# Buck_Converter.net
KiCad netlist of a schematic drawn in Altium Designer
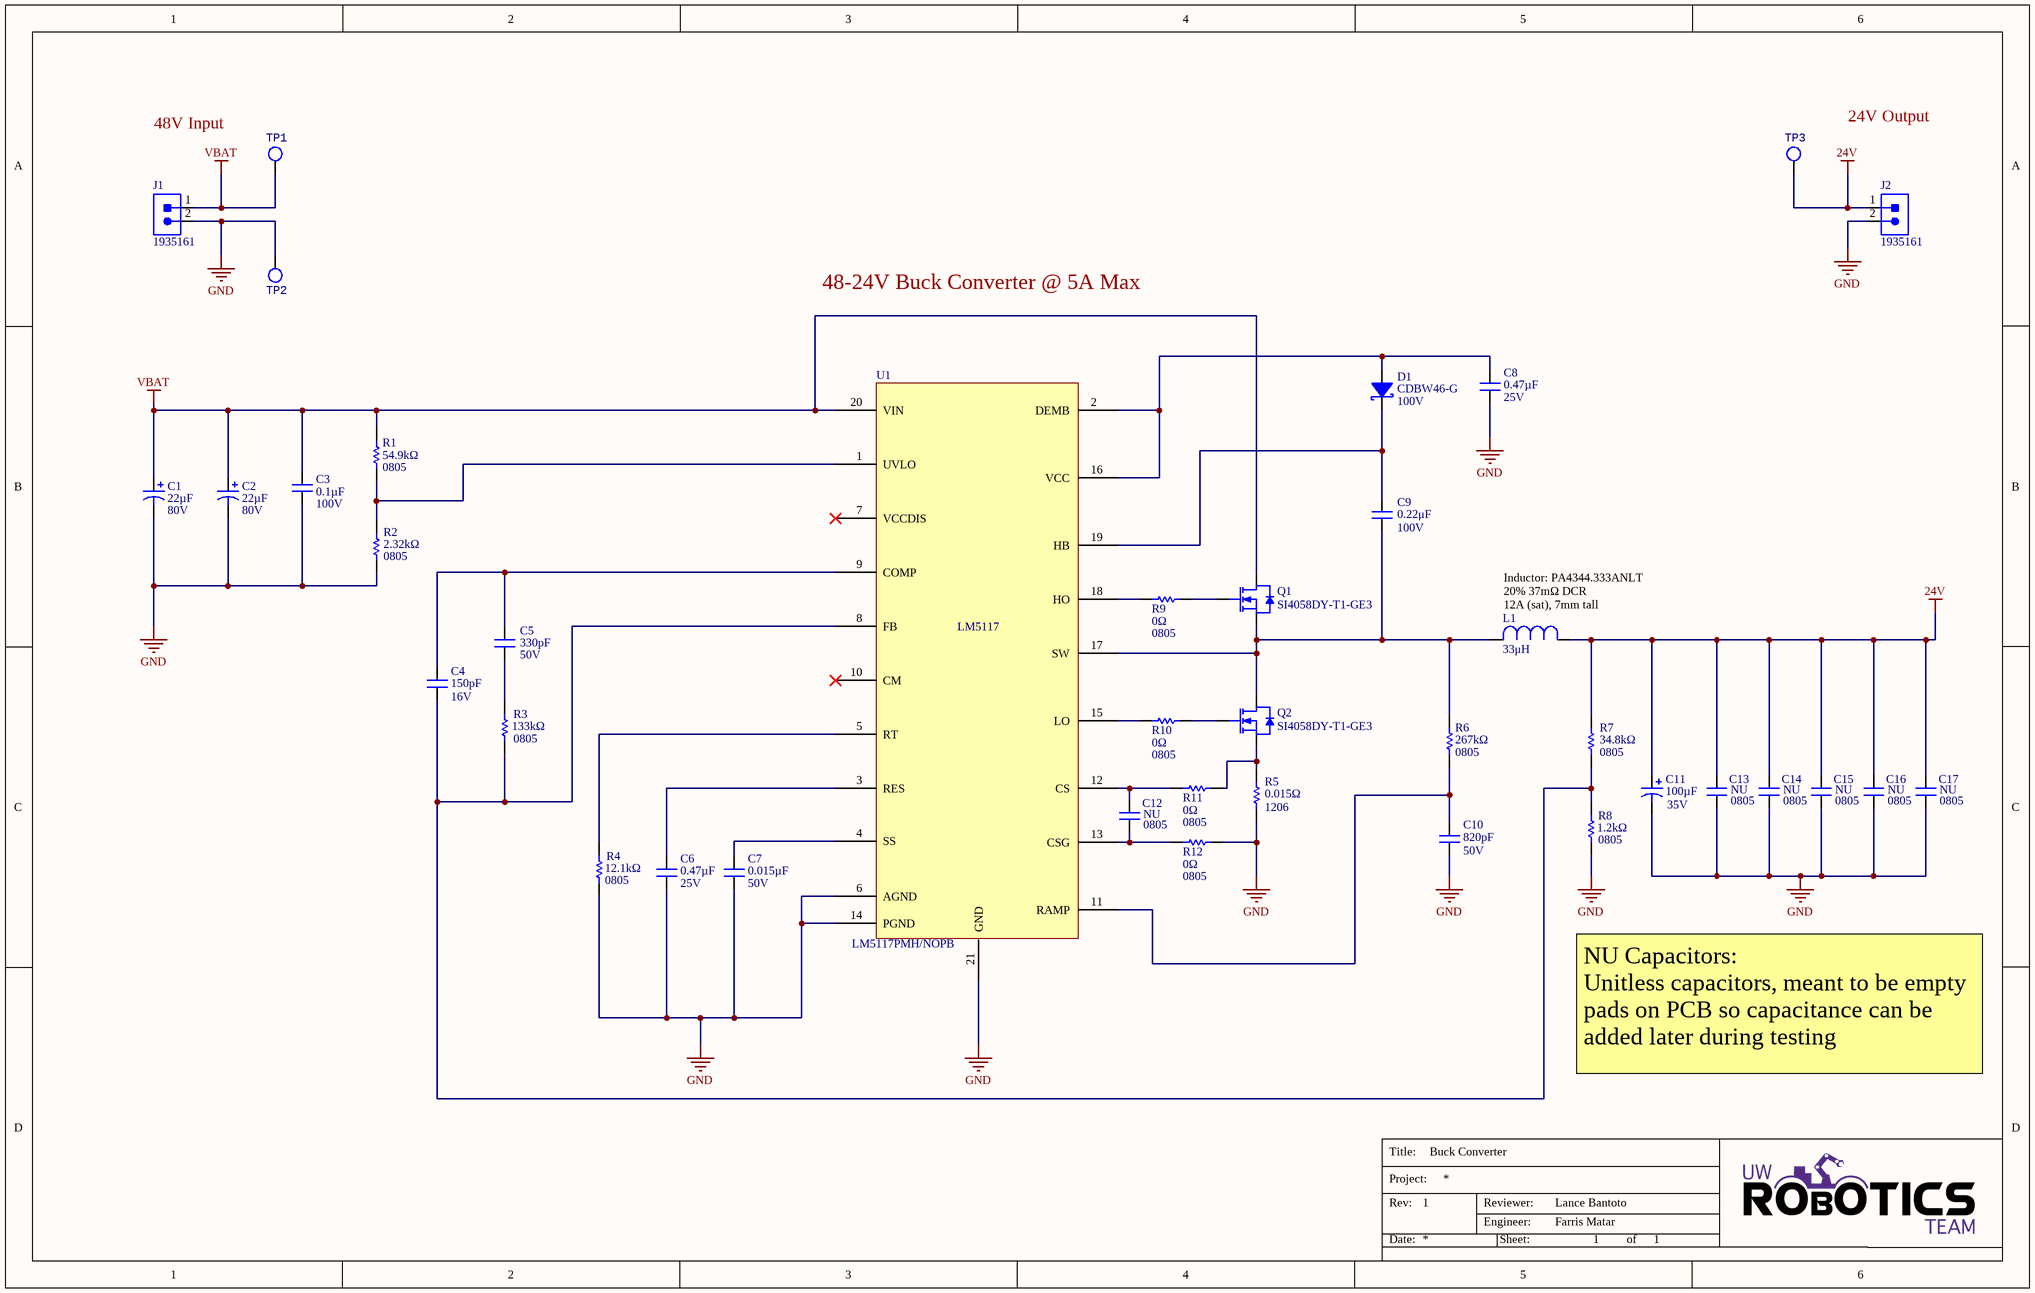
[diagram p0: Buck Converter.SchDoc]

(export (version "E")
  (design (tool "Eeschema 10.0.6"))
  (components
    (comp (ref "C1")
      (value "22µF")
      (footprint "RADIAL_PANASONIC_F")
      (description "CAP ALUM POLY 22UF 20% 80V SMD")
      (fields (field (name "VOLTAGE RATING") "80V") (field (name "Comment") "CAP_22uF_80V_ALUM"))
      (libsource (lib "UWRT_Schematic_Library_2020") (part "CAP_22uF_80V_ALUM"))
    )
    (comp (ref "C2")
      (value "22µF")
      (footprint "RADIAL_PANASONIC_F")
      (description "CAP ALUM POLY 22UF 20% 80V SMD")
      (fields (field (name "VOLTAGE RATING") "80V") (field (name "Comment") "CAP_22uF_80V_ALUM"))
      (libsource (lib "UWRT_Schematic_Library_2020") (part "CAP_22uF_80V_ALUM"))
    )
    (comp (ref "C3")
      (value "0.1µF")
      (footprint "CAP0805")
      (description "CAP CER 0.1UF 100V X7R 0805")
      (fields (field (name "VOLTAGE RATING") "100V") (field (name "Comment") "CAP_0.1uF_100V_0805"))
      (libsource (lib "UWRT_Schematic_Library_2020") (part "CAP_0.1uF_100V_0805"))
    )
    (comp (ref "C4")
      (value "150pF")
      (footprint "CAP0805")
      (description "CAP CER 150PF 16V X7R 0805")
      (fields (field (name "VOLTAGE RATING") "16V") (field (name "Comment") "CAP_150pF_16V_0805"))
      (libsource (lib "UWRT_Schematic_Library_2020") (part "CAP_150pF_16V_0805"))
    )
    (comp (ref "C5")
      (value "330pF")
      (footprint "CAP0805")
      (description "CAP CER 330PF 50V C0G/NPO 0805")
      (fields (field (name "VOLTAGE RATING") "50V") (field (name "Comment") "CAP_330pF_50V_0805"))
      (libsource (lib "UWRT_Schematic_Library_2020") (part "CAP_330pF_50V_0805"))
    )
    (comp (ref "C6")
      (value "0.47µF")
      (footprint "CAP0805")
      (description "CAP CER 0.47UF 25V X5R 0805")
      (fields (field (name "VOLTAGE RATING") "25V") (field (name "Comment") "CAP_0.47uF_25V_0805"))
      (libsource (lib "UWRT_Schematic_Library_2020") (part "CAP_0.47uF_25V_0805"))
    )
    (comp (ref "C7")
      (value "0.015µF")
      (footprint "CAP0805")
      (description "CAP CER 0.015UF 50V C0G 0805")
      (fields (field (name "VOLTAGE RATING") "50V") (field (name "Comment") "CAP_0.015uF_50V_0805"))
      (libsource (lib "UWRT_Schematic_Library_2020") (part "CAP_0.015uF_50V_0805"))
    )
    (comp (ref "C8")
      (value "0.47µF")
      (footprint "CAP0805")
      (description "CAP CER 0.47UF 25V X5R 0805")
      (fields (field (name "VOLTAGE RATING") "25V") (field (name "Comment") "CAP_0.47uF_25V_0805"))
      (libsource (lib "UWRT_Schematic_Library_2020") (part "CAP_0.47uF_25V_0805"))
    )
    (comp (ref "C9")
      (value "0.22μF")
      (footprint "CAP2012")
      (description "CAP CER 0.22UF 100V X7R 0805")
      (fields (field (name "VOLTAGE RATING") "100V") (field (name "Comment") "CAP_0.22uF_100V_0805"))
      (libsource (lib "UWRT_Schematic_Library_2020") (part "CAP_0.22uF_100V_0805"))
    )
    (comp (ref "C10")
      (value "820pF")
      (footprint "CAP0805")
      (description "CAP CER 820PF 50V C0G/NP0 0805")
      (fields (field (name "VOLTAGE RATING") "50V") (field (name "Comment") "CAP_820pF_50V_0805"))
      (libsource (lib "UWRT_Schematic_Library_2020") (part "CAP_820pF_50V_0805"))
    )
    (comp (ref "C11")
      (value "100µF")
      (footprint "RADIAL_CORNELL_D")
      (description "CAP ALUM 100UF 20% 35V SMD")
      (fields (field (name "VOLTAGE RATING") "35V") (field (name "Comment") "CAP_100uF_35V_ALUM"))
      (libsource (lib "UWRT_Schematic_Library_2020") (part "CAP_100uF_35V_ALUM"))
    )
    (comp (ref "C12")
      (value "NU")
      (footprint "CAP0805")
      (description "PLACEHOLDER CAPACITOR 0805")
      (fields (field (name "PACKAGE/FOOTPRINT") "0805") (field (name "Comment") "CAP_NU_0805"))
      (libsource (lib "UWRT_Schematic_Library_2020") (part "CAP_NU_0805"))
    )
    (comp (ref "C13")
      (value "NU")
      (footprint "CAP0805")
      (description "PLACEHOLDER CAPACITOR 0805")
      (fields (field (name "PACKAGE/FOOTPRINT") "0805") (field (name "Comment") "CAP_NU_0805"))
      (libsource (lib "UWRT_Schematic_Library_2020") (part "CAP_NU_0805"))
    )
    (comp (ref "C14")
      (value "NU")
      (footprint "CAP0805")
      (description "PLACEHOLDER CAPACITOR 0805")
      (fields (field (name "PACKAGE/FOOTPRINT") "0805") (field (name "Comment") "CAP_NU_0805"))
      (libsource (lib "UWRT_Schematic_Library_2020") (part "CAP_NU_0805"))
    )
    (comp (ref "C15")
      (value "NU")
      (footprint "CAP0805")
      (description "PLACEHOLDER CAPACITOR 0805")
      (fields (field (name "PACKAGE/FOOTPRINT") "0805") (field (name "Comment") "CAP_NU_0805"))
      (libsource (lib "UWRT_Schematic_Library_2020") (part "CAP_NU_0805"))
    )
    (comp (ref "C16")
      (value "NU")
      (footprint "CAP0805")
      (description "PLACEHOLDER CAPACITOR 0805")
      (fields (field (name "PACKAGE/FOOTPRINT") "0805") (field (name "Comment") "CAP_NU_0805"))
      (libsource (lib "UWRT_Schematic_Library_2020") (part "CAP_NU_0805"))
    )
    (comp (ref "C17")
      (value "NU")
      (footprint "CAP0805")
      (description "PLACEHOLDER CAPACITOR 0805")
      (fields (field (name "PACKAGE/FOOTPRINT") "0805") (field (name "Comment") "CAP_NU_0805"))
      (libsource (lib "UWRT_Schematic_Library_2020") (part "CAP_NU_0805"))
    )
    (comp (ref "D1")
      (value "DIO_SCHOTTKY_100V_150mA")
      (footprint "SOD-123_FLAT")
      (description "DIODE SCHOTTKY 100V 150MA SOD123")
      (fields (field (name "MANUFACTURER PART NUMBER 1") "CDBW46-G") (field (name "VR (MAX)") "100V"))
      (libsource (lib "UWRT_Schematic_Library_2020") (part "DIO_SCHOTTKY_100V_150mA"))
    )
    (comp (ref "J1")
      (value "CON_2POS_SCREW_TERM")
      (footprint "1935161")
      (description "TERM BLK 2POS SIDE ENTRY 5MM")
      (fields (field (name "MANUFACTURER PART NUMBER 1") "1935161"))
      (libsource (lib "") (part "CON_2POS_SCREW_TERM_1"))
    )
    (comp (ref "J2")
      (value "CON_2POS_SCREW_TERM")
      (footprint "1935161")
      (description "TERM BLK 2POS SIDE ENTRY 5MM")
      (fields (field (name "MANUFACTURER PART NUMBER 1") "1935161"))
      (libsource (lib "UWRT_Schematic_Library_2020") (part "CON_2POS_SCREW_TERM"))
    )
    (comp (ref "L1")
      (value "IND_33uH_12.0A")
      (footprint "IND_PULSE_PA4344")
      (description "FIXED IND 33UH 12A 37 MOHM SMD")
      (fields (field (name "INDUCTANCE") "33μH"))
      (libsource (lib "UWRT_Schematic_Library_2020") (part "IND_33uH_12.0A"))
    )
    (comp (ref "Q1")
      (value "NMOS_100V_10.3A")
      (footprint "8-SOIC_NMOS")
      (description "MOSFET N-CH 100V 10.3A 8SOIC")
      (fields (field (name "MANUFACTURER PART NUMBER 1") "SI4058DY-T1-GE3"))
      (libsource (lib "UWRT_Schematic_Library_2020") (part "NMOS_100V_10.3A"))
    )
    (comp (ref "Q2")
      (value "NMOS_100V_10.3A")
      (footprint "8-SOIC_NMOS")
      (description "MOSFET N-CH 100V 10.3A 8SOIC")
      (fields (field (name "MANUFACTURER PART NUMBER 1") "SI4058DY-T1-GE3"))
      (libsource (lib "UWRT_Schematic_Library_2020") (part "NMOS_100V_10.3A"))
    )
    (comp (ref "R1")
      (value "54.9kΩ")
      (footprint "RES0805")
      (description "RES SMD 54.9K OHM 1% 1/8W 0805")
      (fields (field (name "PACKAGE/FOOTPRINT") "0805") (field (name "Comment") "RES_54.9kΩ_0805_1%"))
      (libsource (lib "UWRT_Schematic_Library_2020") (part "RES_54.9kΩ_0805_1%"))
    )
    (comp (ref "R2")
      (value "2.32kΩ")
      (footprint "RES0805")
      (description "RES 2.32K OHM 1% 1/4W 0805")
      (fields (field (name "PACKAGE/FOOTPRINT") "0805") (field (name "Comment") "RES_2.32kΩ_0805_1%"))
      (libsource (lib "UWRT_Schematic_Library_2020") (part "RES_2.32kΩ_0805_1%"))
    )
    (comp (ref "R3")
      (value "133kΩ")
      (footprint "RES0805")
      (description "RES SMD 133K OHM 1% 1/8W 0805")
      (fields (field (name "PACKAGE/FOOTPRINT") "0805") (field (name "Comment") "RES_133kΩ_0805_1%"))
      (libsource (lib "UWRT_Schematic_Library_2020") (part "RES_133kΩ_0805_1%"))
    )
    (comp (ref "R4")
      (value "12.1kΩ")
      (footprint "RES0805")
      (description "RES 12.1K OHM 1% 1/4W 0805")
      (fields (field (name "PACKAGE/FOOTPRINT") "0805") (field (name "Comment") "RES_12.1kΩ_0805_1%"))
      (libsource (lib "UWRT_Schematic_Library_2020") (part "RES_12.1kΩ_0805_1%"))
    )
    (comp (ref "R5")
      (value "0.015Ω")
      (footprint "RES1206")
      (description "RES 0.015 OHM 1% 1/2W 1206")
      (fields (field (name "PACKAGE/FOOTPRINT") "1206") (field (name "Comment") "RES_0.015Ω_1206_1%"))
      (libsource (lib "UWRT_Schematic_Library_2020") (part "RES_0.015Ω_1206_1%"))
    )
    (comp (ref "R6")
      (value "267kΩ")
      (footprint "RES0805")
      (description "RES SMD 267K OHM 1% 1/8W 0805")
      (fields (field (name "PACKAGE/FOOTPRINT") "0805") (field (name "Comment") "RES_267kΩ_0805_1%"))
      (libsource (lib "UWRT_Schematic_Library_2020") (part "RES_267kΩ_0805_1%"))
    )
    (comp (ref "R7")
      (value "34.8kΩ")
      (footprint "RES0805")
      (description "RES 34.8K OHM 1% 1/8W 0805")
      (fields (field (name "PACKAGE/FOOTPRINT") "0805") (field (name "Comment") "RES_34.8kΩ_0805_1%"))
      (libsource (lib "UWRT_Schematic_Library_2020") (part "RES_34.8kΩ_0805_1%"))
    )
    (comp (ref "R8")
      (value "1.2kΩ")
      (footprint "RES0805")
      (description "RES SMD 1.2K OHM 1% 1/8W 0805")
      (fields (field (name "PACKAGE/FOOTPRINT") "0805") (field (name "Comment") "RES_1.2kΩ_0805"))
      (libsource (lib "UWRT_Schematic_Library_2020") (part "RES_1.2kΩ_0805_1%"))
    )
    (comp (ref "R9")
      (value "0Ω")
      (footprint "RES0805")
      (description "RES 0 OHM JUMPER 1/8W 0805")
      (fields
        (field (name "PACKAGE/FOOTPRINT") "0805")
        (field (name "LCSC PART #") "C17477")
        (field (name "Comment") "RES_0Ω_0805")
      )
      (libsource (lib "UWRT_Schematic_Library_2020") (part "RES_0Ω_0805"))
    )
    (comp (ref "R10")
      (value "0Ω")
      (footprint "RES0805")
      (description "RES 0 OHM JUMPER 1/8W 0805")
      (fields
        (field (name "PACKAGE/FOOTPRINT") "0805")
        (field (name "LCSC PART #") "C17477")
        (field (name "Comment") "RES_0Ω_0805")
      )
      (libsource (lib "UWRT_Schematic_Library_2020") (part "RES_0Ω_0805"))
    )
    (comp (ref "R11")
      (value "0Ω")
      (footprint "RES0805")
      (description "RES 0 OHM JUMPER 1/8W 0805")
      (fields
        (field (name "PACKAGE/FOOTPRINT") "0805")
        (field (name "LCSC PART #") "C17477")
        (field (name "Comment") "RES_0Ω_0805")
      )
      (libsource (lib "UWRT_Schematic_Library_2020") (part "RES_0Ω_0805"))
    )
    (comp (ref "R12")
      (value "0Ω")
      (footprint "RES0805")
      (description "RES 0 OHM JUMPER 1/8W 0805")
      (fields
        (field (name "PACKAGE/FOOTPRINT") "0805")
        (field (name "LCSC PART #") "C17477")
        (field (name "Comment") "RES_0Ω_0805")
      )
      (libsource (lib "UWRT_Schematic_Library_2020") (part "RES_0Ω_0805"))
    )
    (comp (ref "TP1")
      (value "TESTPOINT_LOOP")
      (footprint "TESTPOINT_LOOP")
      (description "TESTPOINT THRUHOLE")
      (libsource (lib "UWRT_Schematic_Library_2020") (part "TESTPOINT_LOOP"))
    )
    (comp (ref "TP2")
      (value "TESTPOINT_LOOP")
      (footprint "TESTPOINT_LOOP")
      (description "TESTPOINT THRUHOLE")
      (libsource (lib "UWRT_Schematic_Library_2020") (part "TESTPOINT_LOOP"))
    )
    (comp (ref "TP3")
      (value "TESTPOINT_LOOP")
      (footprint "TESTPOINT_LOOP")
      (description "TESTPOINT THRUHOLE")
      (libsource (lib "UWRT_Schematic_Library_2020") (part "TESTPOINT_LOOP"))
    )
    (comp (ref "U1")
      (value "BUCK_LM5117PWP")
      (footprint "HTSSOP")
      (description "IC REG CTRLR BUCK 20TSSOP")
      (fields (field (name "MANUFACTURER PART NUMBER 1") "LM5117PMH/NOPB"))
      (libsource (lib "UWRT_Schematic_Library_2020") (part "BUCK_LM5117PWP"))
    )
  )
  (nets
    (net (code "1") (name "24V") (class "Default")
      (node (ref "C11") (pin "1") (pinfunction "1_1") (pintype "passive"))
      (node (ref "C13") (pin "2") (pinfunction "2_2") (pintype "passive"))
      (node (ref "C14") (pin "2") (pinfunction "2_2") (pintype "passive"))
      (node (ref "C15") (pin "2") (pinfunction "2_2") (pintype "passive"))
      (node (ref "C16") (pin "2") (pinfunction "2_2") (pintype "passive"))
      (node (ref "C17") (pin "2") (pinfunction "2_2") (pintype "passive"))
      (node (ref "J2") (pin "1") (pinfunction "1_1") (pintype "passive"))
      (node (ref "L1") (pin "1") (pinfunction "1_1") (pintype "passive"))
      (node (ref "R7") (pin "2") (pinfunction "2_2") (pintype "passive"))
      (node (ref "TP3") (pin "1") (pintype "passive"))
    )
    (net (code "2") (name "GND") (class "Default")
      (node (ref "C1") (pin "2") (pinfunction "2_2") (pintype "passive"))
      (node (ref "C10") (pin "1") (pinfunction "1_1") (pintype "passive"))
      (node (ref "C11") (pin "2") (pinfunction "2_2") (pintype "passive"))
      (node (ref "C13") (pin "1") (pinfunction "1_1") (pintype "passive"))
      (node (ref "C14") (pin "1") (pinfunction "1_1") (pintype "passive"))
      (node (ref "C15") (pin "1") (pinfunction "1_1") (pintype "passive"))
      (node (ref "C16") (pin "1") (pinfunction "1_1") (pintype "passive"))
      (node (ref "C17") (pin "1") (pinfunction "1_1") (pintype "passive"))
      (node (ref "C2") (pin "2") (pinfunction "2_2") (pintype "passive"))
      (node (ref "C3") (pin "1") (pinfunction "1_1") (pintype "passive"))
      (node (ref "C6") (pin "1") (pinfunction "1_1") (pintype "passive"))
      (node (ref "C7") (pin "1") (pinfunction "1_1") (pintype "passive"))
      (node (ref "C8") (pin "1") (pinfunction "1_1") (pintype "passive"))
      (node (ref "J1") (pin "2") (pinfunction "2_2") (pintype "passive"))
      (node (ref "J2") (pin "2") (pinfunction "2_2") (pintype "passive"))
      (node (ref "R12") (pin "2") (pinfunction "2_2") (pintype "passive"))
      (node (ref "R2") (pin "1") (pinfunction "1_1") (pintype "passive"))
      (node (ref "R4") (pin "1") (pinfunction "1_1") (pintype "passive"))
      (node (ref "R5") (pin "1") (pinfunction "1_1") (pintype "passive"))
      (node (ref "R8") (pin "1") (pinfunction "1_1") (pintype "passive"))
      (node (ref "TP2") (pin "1") (pintype "passive"))
      (node (ref "U1") (pin "14") (pinfunction "PGND_14") (pintype "passive"))
      (node (ref "U1") (pin "21") (pinfunction "GND_21") (pintype "passive"))
      (node (ref "U1") (pin "6") (pinfunction "AGND_6") (pintype "passive"))
    )
    (net (code "3") (name "Net-(C5-Pad1)") (class "Default")
      (node (ref "C5") (pin "1") (pinfunction "1_1") (pintype "passive"))
      (node (ref "R3") (pin "2") (pinfunction "2_2") (pintype "passive"))
    )
    (net (code "4") (name "Net-(D1-Anode)") (class "Default")
      (node (ref "C8") (pin "2") (pinfunction "2_2") (pintype "passive"))
      (node (ref "D1") (pin "1") (pinfunction "Anode_1") (pintype "passive"))
      (node (ref "U1") (pin "16") (pinfunction "VCC_16") (pintype "passive"))
      (node (ref "U1") (pin "2") (pinfunction "DEMB_2") (pintype "passive"))
    )
    (net (code "5") (name "Net-(D1-Cathode)") (class "Default")
      (node (ref "C9") (pin "2") (pinfunction "2_2") (pintype "passive"))
      (node (ref "D1") (pin "2") (pinfunction "Cathode_2") (pintype "passive"))
      (node (ref "U1") (pin "19") (pinfunction "HB_19") (pintype "passive"))
    )
    (net (code "6") (name "Net-(Q1-Gate)") (class "Default")
      (node (ref "Q1") (pin "1") (pinfunction "Gate_1") (pintype "passive"))
      (node (ref "R9") (pin "2") (pinfunction "2_2") (pintype "passive"))
    )
    (net (code "7") (name "Net-(Q1-Source)") (class "Default")
      (node (ref "C9") (pin "1") (pinfunction "1_1") (pintype "passive"))
      (node (ref "L1") (pin "2") (pinfunction "2_2") (pintype "passive"))
      (node (ref "Q1") (pin "2") (pinfunction "Source_2") (pintype "passive"))
      (node (ref "Q2") (pin "3") (pinfunction "Drain_3") (pintype "passive"))
      (node (ref "R6") (pin "2") (pinfunction "2_2") (pintype "passive"))
      (node (ref "U1") (pin "17") (pinfunction "SW_17") (pintype "passive"))
    )
    (net (code "8") (name "Net-(Q2-Gate)") (class "Default")
      (node (ref "Q2") (pin "1") (pinfunction "Gate_1") (pintype "passive"))
      (node (ref "R10") (pin "2") (pinfunction "2_2") (pintype "passive"))
    )
    (net (code "9") (name "Net-(Q2-Source)") (class "Default")
      (node (ref "Q2") (pin "2") (pinfunction "Source_2") (pintype "passive"))
      (node (ref "R11") (pin "2") (pinfunction "2_2") (pintype "passive"))
      (node (ref "R5") (pin "2") (pinfunction "2_2") (pintype "passive"))
    )
    (net (code "10") (name "Net-(U1-COMP)") (class "Default")
      (node (ref "C4") (pin "2") (pinfunction "2_2") (pintype "passive"))
      (node (ref "C5") (pin "2") (pinfunction "2_2") (pintype "passive"))
      (node (ref "U1") (pin "9") (pinfunction "COMP_9") (pintype "passive"))
    )
    (net (code "11") (name "Net-(U1-CS)") (class "Default")
      (node (ref "C12") (pin "2") (pinfunction "2_2") (pintype "passive"))
      (node (ref "R11") (pin "1") (pinfunction "1_1") (pintype "passive"))
      (node (ref "U1") (pin "12") (pinfunction "CS_12") (pintype "passive"))
    )
    (net (code "12") (name "Net-(U1-CSG)") (class "Default")
      (node (ref "C12") (pin "1") (pinfunction "1_1") (pintype "passive"))
      (node (ref "R12") (pin "1") (pinfunction "1_1") (pintype "passive"))
      (node (ref "U1") (pin "13") (pinfunction "CSG_13") (pintype "passive"))
    )
    (net (code "13") (name "Net-(U1-FB)") (class "Default")
      (node (ref "C4") (pin "1") (pinfunction "1_1") (pintype "passive"))
      (node (ref "R3") (pin "1") (pinfunction "1_1") (pintype "passive"))
      (node (ref "R7") (pin "1") (pinfunction "1_1") (pintype "passive"))
      (node (ref "R8") (pin "2") (pinfunction "2_2") (pintype "passive"))
      (node (ref "U1") (pin "8") (pinfunction "FB_8") (pintype "passive"))
    )
    (net (code "14") (name "Net-(U1-HO)") (class "Default")
      (node (ref "R9") (pin "1") (pinfunction "1_1") (pintype "passive"))
      (node (ref "U1") (pin "18") (pinfunction "HO_18") (pintype "passive"))
    )
    (net (code "15") (name "Net-(U1-LO)") (class "Default")
      (node (ref "R10") (pin "1") (pinfunction "1_1") (pintype "passive"))
      (node (ref "U1") (pin "15") (pinfunction "LO_15") (pintype "passive"))
    )
    (net (code "16") (name "Net-(U1-RAMP)") (class "Default")
      (node (ref "C10") (pin "2") (pinfunction "2_2") (pintype "passive"))
      (node (ref "R6") (pin "1") (pinfunction "1_1") (pintype "passive"))
      (node (ref "U1") (pin "11") (pinfunction "RAMP_11") (pintype "passive"))
    )
    (net (code "17") (name "Net-(U1-RES)") (class "Default")
      (node (ref "C6") (pin "2") (pinfunction "2_2") (pintype "passive"))
      (node (ref "U1") (pin "3") (pinfunction "RES_3") (pintype "passive"))
    )
    (net (code "18") (name "Net-(U1-RT)") (class "Default")
      (node (ref "R4") (pin "2") (pinfunction "2_2") (pintype "passive"))
      (node (ref "U1") (pin "5") (pinfunction "RT_5") (pintype "passive"))
    )
    (net (code "19") (name "Net-(U1-SS)") (class "Default")
      (node (ref "C7") (pin "2") (pinfunction "2_2") (pintype "passive"))
      (node (ref "U1") (pin "4") (pinfunction "SS_4") (pintype "passive"))
    )
    (net (code "20") (name "Net-(U1-UVLO)") (class "Default")
      (node (ref "R1") (pin "1") (pinfunction "1_1") (pintype "passive"))
      (node (ref "R2") (pin "2") (pinfunction "2_2") (pintype "passive"))
      (node (ref "U1") (pin "1") (pinfunction "UVLO_1") (pintype "passive"))
    )
    (net (code "21") (name "VBAT") (class "Default")
      (node (ref "C1") (pin "1") (pinfunction "1_1") (pintype "passive"))
      (node (ref "C2") (pin "1") (pinfunction "1_1") (pintype "passive"))
      (node (ref "C3") (pin "2") (pinfunction "2_2") (pintype "passive"))
      (node (ref "J1") (pin "1") (pinfunction "1_1") (pintype "passive"))
      (node (ref "Q1") (pin "3") (pinfunction "Drain_3") (pintype "passive"))
      (node (ref "R1") (pin "2") (pinfunction "2_2") (pintype "passive"))
      (node (ref "TP1") (pin "1") (pintype "passive"))
      (node (ref "U1") (pin "20") (pinfunction "VIN_20") (pintype "passive"))
    )
    (net (code "22") (name "unconnected-(U1-CM-Pad10)") (class "Default")
      (node (ref "U1") (pin "10") (pinfunction "CM_10") (pintype "passive+no_connect"))
    )
    (net (code "23") (name "unconnected-(U1-VCCDIS-Pad7)") (class "Default")
      (node (ref "U1") (pin "7") (pinfunction "VCCDIS_7") (pintype "passive+no_connect"))
    )
  )
)
